# pgacontrol-mini.net
KiCad netlist of a schematic drawn in EAGLE
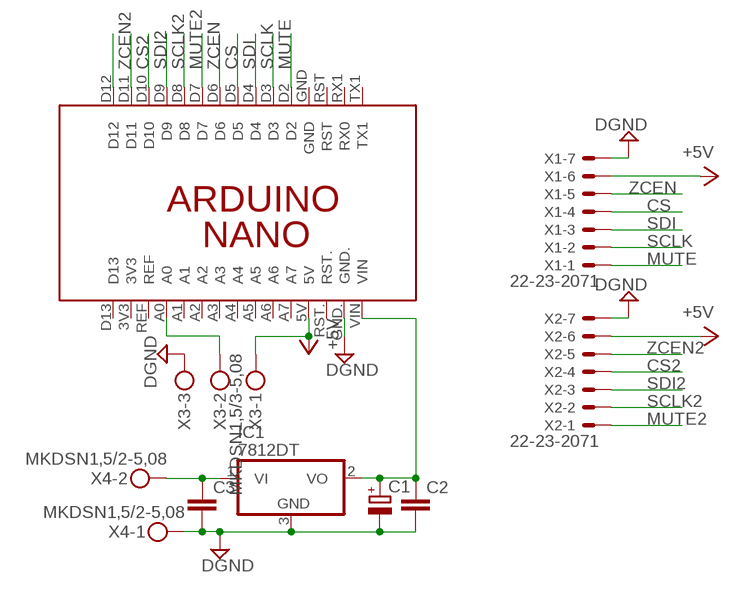
[diagram p0: schematic, sheet 1]

(export (version "E")
  (design (tool "Eeschema 10.0.6"))
  (components
    (comp (ref "C1")
      (value "CPOL-EUSMCD")
      (footprint "eagle-import:SMC_D")
      (libsource (lib "eagle-import") (part "CPOL-EUSMCD"))
    )
    (comp (ref "C2")
      (value "C-EUC1206")
      (footprint "eagle-import:C1206")
      (libsource (lib "eagle-import") (part "C-EUC1206"))
    )
    (comp (ref "C3")
      (value "C-EUC1206")
      (footprint "eagle-import:C1206")
      (libsource (lib "eagle-import") (part "C-EUC1206"))
    )
    (comp (ref "IC1")
      (value "7812DT")
      (footprint "eagle-import:TO252")
      (libsource (lib "eagle-import") (part "78DT12"))
    )
    (comp (ref "PCB1")
      (value "ARDUINO_NANO")
      (footprint "eagle-import:ARDUINO_NANO")
      (libsource (lib "eagle-import") (part "ARDUINO_NANO"))
    )
    (comp (ref "X1")
      (value "22-23-2071")
      (footprint "eagle-import:22-23-2071")
      (fields (field (name "MF") "MOLEX"))
      (libsource (lib "eagle-import") (part "22-23-2071"))
    )
    (comp (ref "X2")
      (value "22-23-2071")
      (footprint "eagle-import:22-23-2071")
      (fields (field (name "MF") "MOLEX"))
      (libsource (lib "eagle-import") (part "22-23-2071"))
    )
    (comp (ref "X3")
      (value "MKDSN1,5/3-5,08")
      (footprint "eagle-import:MKDSN1,5_3-5,08")
      (libsource (lib "eagle-import") (part "MKDSN1,5/3-5,08"))
    )
    (comp (ref "X4")
      (value "MKDSN1,5/2-5,08")
      (footprint "eagle-import:MKDSN1,5_2-5,08")
      (libsource (lib "eagle-import") (part "MKDSN1,5/2-5,08"))
    )
  )
  (nets
    (net (code "1") (name "+5V") (class "Default")
      (node (ref "PCB1") (pin "5V") (pinfunction "5V_5V") (pintype "bidirectional"))
      (node (ref "X1") (pin "6") (pinfunction "S_6") (pintype "passive"))
      (node (ref "X2") (pin "6") (pinfunction "S_6") (pintype "passive"))
      (node (ref "X3") (pin "1") (pinfunction "KL_1") (pintype "passive"))
    )
    (net (code "2") (name "/CS") (class "Default")
      (node (ref "PCB1") (pin "D5") (pinfunction "D5_D5") (pintype "bidirectional"))
      (node (ref "X1") (pin "4") (pinfunction "S_4") (pintype "passive"))
    )
    (net (code "3") (name "/CS2") (class "Default")
      (node (ref "PCB1") (pin "D10") (pinfunction "D10_D10") (pintype "bidirectional"))
      (node (ref "X2") (pin "4") (pinfunction "S_4") (pintype "passive"))
    )
    (net (code "4") (name "/MUTE") (class "Default")
      (node (ref "PCB1") (pin "D2") (pinfunction "D2_D2") (pintype "bidirectional"))
      (node (ref "X1") (pin "1") (pinfunction "S_1") (pintype "passive"))
    )
    (net (code "5") (name "/MUTE2") (class "Default")
      (node (ref "PCB1") (pin "D7") (pinfunction "D7_D7") (pintype "bidirectional"))
      (node (ref "X2") (pin "1") (pinfunction "S_1") (pintype "passive"))
    )
    (net (code "6") (name "/SCLK") (class "Default")
      (node (ref "PCB1") (pin "D3") (pinfunction "D3_D3") (pintype "bidirectional"))
      (node (ref "X1") (pin "2") (pinfunction "S_2") (pintype "passive"))
    )
    (net (code "7") (name "/SCLK2") (class "Default")
      (node (ref "PCB1") (pin "D8") (pinfunction "D8_D8") (pintype "bidirectional"))
      (node (ref "X2") (pin "2") (pinfunction "S_2") (pintype "passive"))
    )
    (net (code "8") (name "/SDI") (class "Default")
      (node (ref "PCB1") (pin "D4") (pinfunction "D4_D4") (pintype "bidirectional"))
      (node (ref "X1") (pin "3") (pinfunction "S_3") (pintype "passive"))
    )
    (net (code "9") (name "/SDI2") (class "Default")
      (node (ref "PCB1") (pin "D9") (pinfunction "D9_D9") (pintype "bidirectional"))
      (node (ref "X2") (pin "3") (pinfunction "S_3") (pintype "passive"))
    )
    (net (code "10") (name "/ZCEN") (class "Default")
      (node (ref "PCB1") (pin "D6") (pinfunction "D6_D6") (pintype "bidirectional"))
      (node (ref "X1") (pin "5") (pinfunction "S_5") (pintype "passive"))
    )
    (net (code "11") (name "/ZCEN2") (class "Default")
      (node (ref "PCB1") (pin "D11") (pinfunction "D11_D11") (pintype "bidirectional"))
      (node (ref "X2") (pin "5") (pinfunction "S_5") (pintype "passive"))
    )
    (net (code "12") (name "DGND") (class "Default")
      (node (ref "C1") (pin "-") (pinfunction "-_-") (pintype "passive"))
      (node (ref "C2") (pin "2") (pinfunction "2_2") (pintype "passive"))
      (node (ref "C3") (pin "2") (pinfunction "2_2") (pintype "passive"))
      (node (ref "IC1") (pin "3") (pinfunction "GND_3") (pintype "passive"))
      (node (ref "PCB1") (pin "GND.") (pinfunction "GND._GND.") (pintype "bidirectional"))
      (node (ref "X1") (pin "7") (pinfunction "S_7") (pintype "passive"))
      (node (ref "X2") (pin "7") (pinfunction "S_7") (pintype "passive"))
      (node (ref "X3") (pin "3") (pinfunction "KL_3") (pintype "passive"))
      (node (ref "X4") (pin "1") (pinfunction "KL_1") (pintype "passive"))
    )
    (net (code "13") (name "Net-(IC1-VI)") (class "Default")
      (node (ref "C3") (pin "1") (pinfunction "1_1") (pintype "passive"))
      (node (ref "IC1") (pin "1") (pinfunction "VI_1") (pintype "input"))
      (node (ref "X4") (pin "2") (pinfunction "KL_2") (pintype "passive"))
    )
    (net (code "14") (name "Net-(IC1-VO)") (class "Default")
      (node (ref "C1") (pin "+") (pinfunction "+_+") (pintype "passive"))
      (node (ref "C2") (pin "1") (pinfunction "1_1") (pintype "passive"))
      (node (ref "IC1") (pin "2") (pinfunction "VO_2") (pintype "passive"))
      (node (ref "PCB1") (pin "VIN") (pinfunction "VIN_VIN") (pintype "bidirectional"))
    )
    (net (code "15") (name "Net-(X3B-KL)") (class "Default")
      (node (ref "PCB1") (pin "A0") (pinfunction "A0_A0") (pintype "bidirectional"))
      (node (ref "X3") (pin "2") (pinfunction "KL_2") (pintype "passive"))
    )
    (net (code "16") (name "unconnected-(PCB1-Pad3V3)") (class "Default")
      (node (ref "PCB1") (pin "3V3") (pinfunction "3V3_3V3") (pintype "bidirectional"))
    )
    (net (code "17") (name "unconnected-(PCB1-PadA1)") (class "Default")
      (node (ref "PCB1") (pin "A1") (pinfunction "A1_A1") (pintype "bidirectional"))
    )
    (net (code "18") (name "unconnected-(PCB1-PadA2)") (class "Default")
      (node (ref "PCB1") (pin "A2") (pinfunction "A2_A2") (pintype "bidirectional"))
    )
    (net (code "19") (name "unconnected-(PCB1-PadA3)") (class "Default")
      (node (ref "PCB1") (pin "A3") (pinfunction "A3_A3") (pintype "bidirectional"))
    )
    (net (code "20") (name "unconnected-(PCB1-PadA4)") (class "Default")
      (node (ref "PCB1") (pin "A4") (pinfunction "A4_A4") (pintype "bidirectional"))
    )
    (net (code "21") (name "unconnected-(PCB1-PadA5)") (class "Default")
      (node (ref "PCB1") (pin "A5") (pinfunction "A5_A5") (pintype "bidirectional"))
    )
    (net (code "22") (name "unconnected-(PCB1-PadA6)") (class "Default")
      (node (ref "PCB1") (pin "A6") (pinfunction "A6_A6") (pintype "bidirectional"))
    )
    (net (code "23") (name "unconnected-(PCB1-PadA7)") (class "Default")
      (node (ref "PCB1") (pin "A7") (pinfunction "A7_A7") (pintype "bidirectional"))
    )
    (net (code "24") (name "unconnected-(PCB1-PadD12)") (class "Default")
      (node (ref "PCB1") (pin "D12") (pinfunction "D12_D12") (pintype "bidirectional"))
    )
    (net (code "25") (name "unconnected-(PCB1-PadD13)") (class "Default")
      (node (ref "PCB1") (pin "D13") (pinfunction "D13_D13") (pintype "bidirectional"))
    )
    (net (code "26") (name "unconnected-(PCB1-PadGND)") (class "Default")
      (node (ref "PCB1") (pin "GND") (pinfunction "GND_GND") (pintype "bidirectional"))
    )
    (net (code "27") (name "unconnected-(PCB1-PadREF)") (class "Default")
      (node (ref "PCB1") (pin "REF") (pinfunction "REF_REF") (pintype "bidirectional"))
    )
    (net (code "28") (name "unconnected-(PCB1-PadRST)") (class "Default")
      (node (ref "PCB1") (pin "RST") (pinfunction "RST_RST") (pintype "bidirectional"))
    )
    (net (code "29") (name "unconnected-(PCB1-PadRST.)") (class "Default")
      (node (ref "PCB1") (pin "RST.") (pinfunction "RST._RST.") (pintype "bidirectional"))
    )
    (net (code "30") (name "unconnected-(PCB1-PadTX1)") (class "Default")
      (node (ref "PCB1") (pin "TX1") (pinfunction "TX1_TX1") (pintype "bidirectional"))
    )
    (net (code "31") (name "unconnected-(PCB1-RX0-PadRX1)") (class "Default")
      (node (ref "PCB1") (pin "RX1") (pinfunction "RX0_RX1") (pintype "bidirectional"))
    )
  )
)
